# Proto-Pi-B.net
KiCad netlist of a schematic drawn in EAGLE
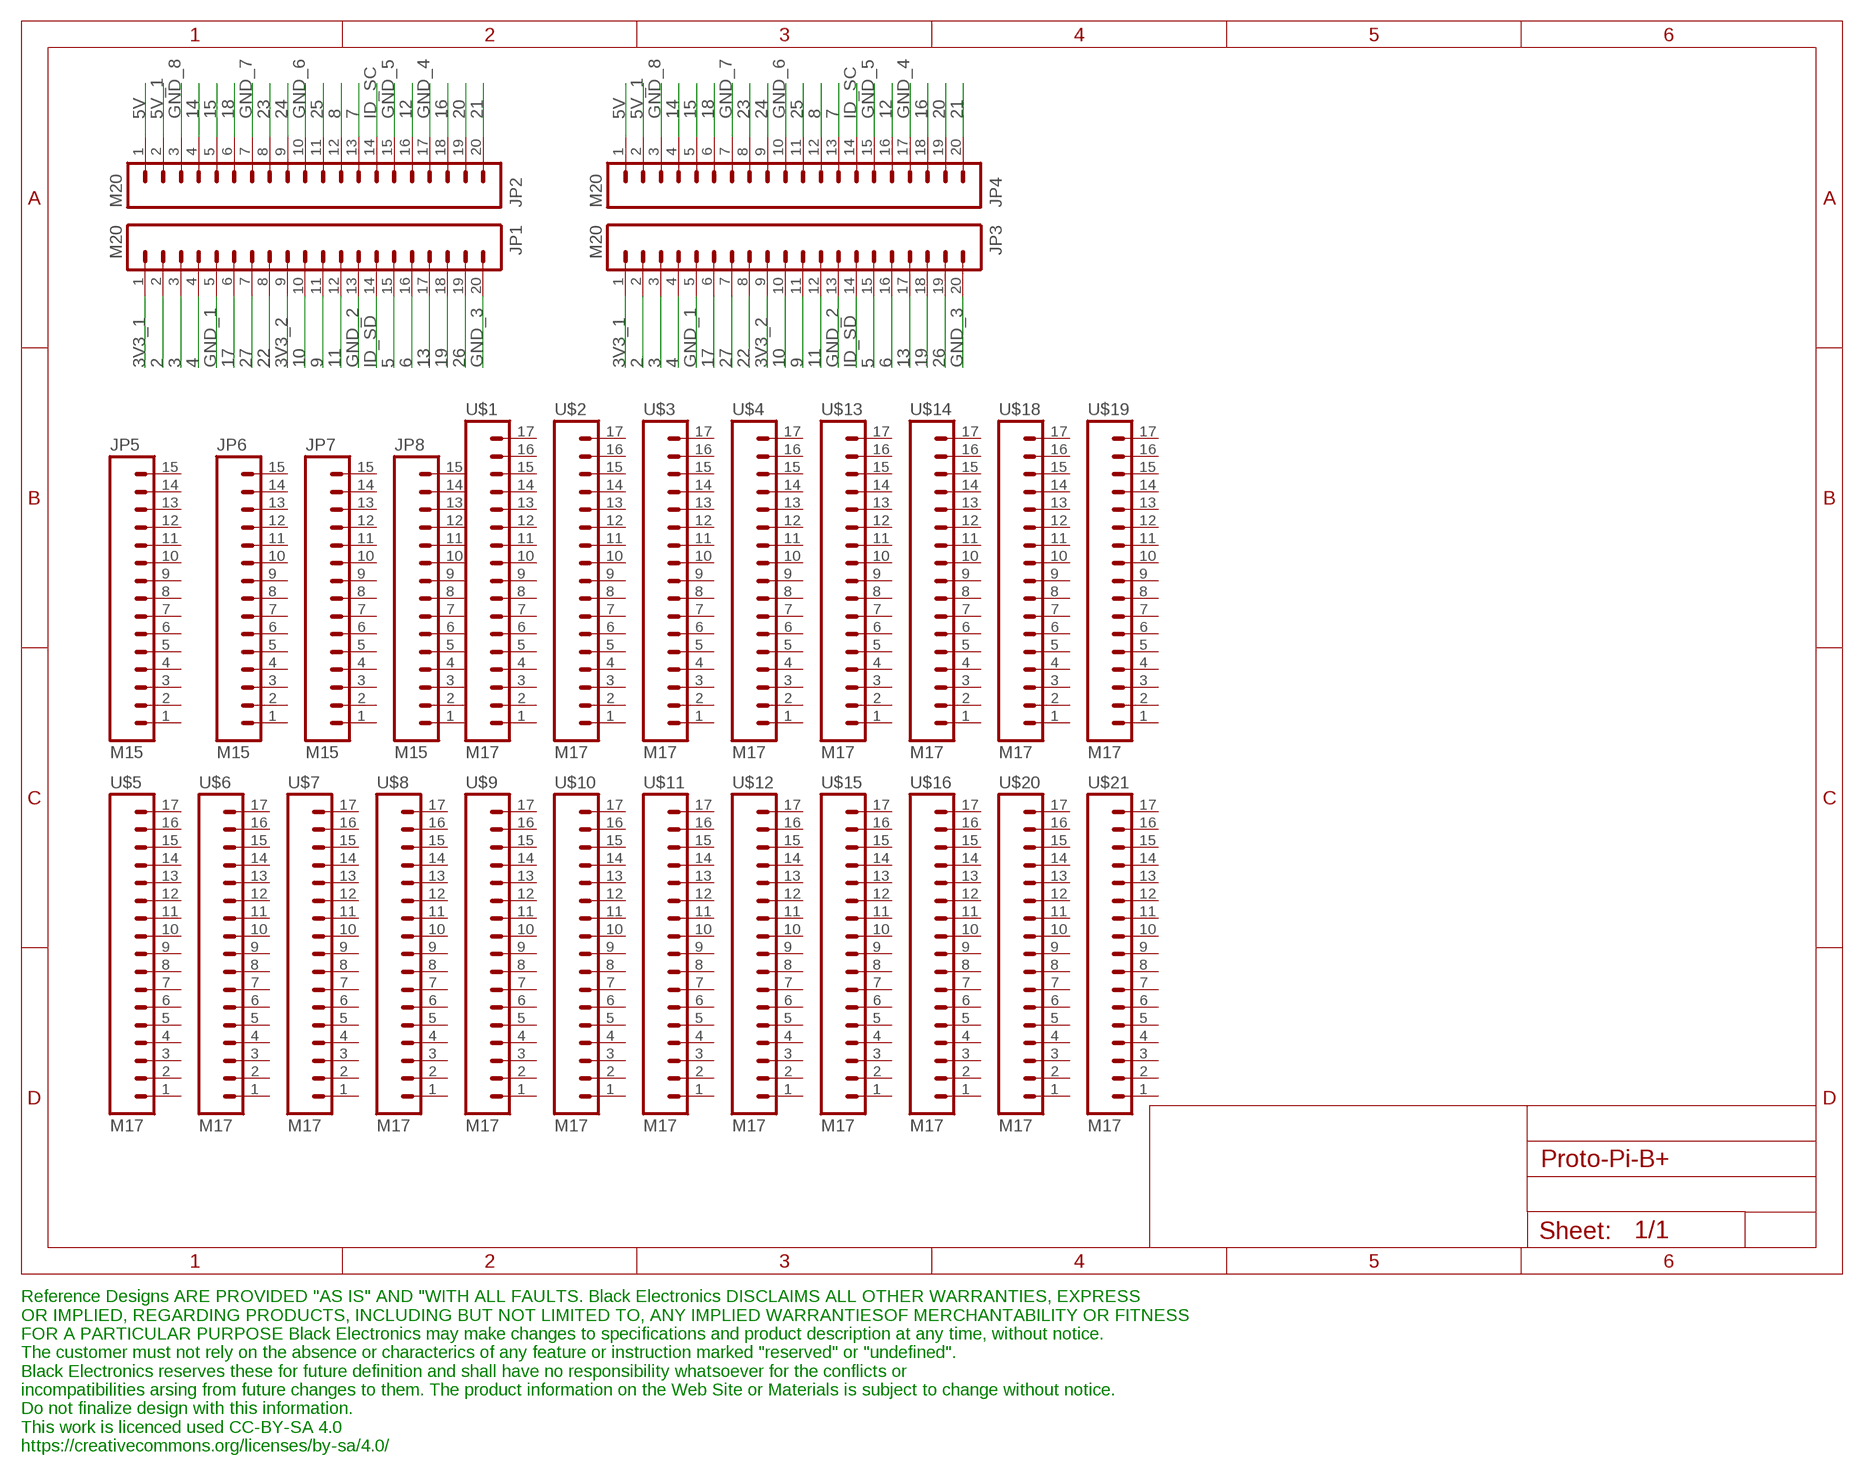
[diagram p0: schematic, sheet 1]

(export (version "E")
  (design (tool "Eeschema 10.0.6"))
  (components
    (comp (ref "JP1")
      (value "M20")
      (footprint "eagle-import:1X20")
      (libsource (lib "eagle-import") (part "M20"))
    )
    (comp (ref "JP2")
      (value "M20")
      (footprint "eagle-import:1X20")
      (libsource (lib "eagle-import") (part "M20"))
    )
    (comp (ref "JP3")
      (value "M20")
      (footprint "eagle-import:1X20")
      (libsource (lib "eagle-import") (part "M20"))
    )
    (comp (ref "JP4")
      (value "M20")
      (footprint "eagle-import:1X20")
      (libsource (lib "eagle-import") (part "M20"))
    )
    (comp (ref "JP5")
      (value "M15")
      (footprint "eagle-import:1X15")
      (libsource (lib "eagle-import") (part "M15"))
    )
    (comp (ref "JP6")
      (value "M15")
      (footprint "eagle-import:1X15")
      (libsource (lib "eagle-import") (part "M15"))
    )
    (comp (ref "JP7")
      (value "M15")
      (footprint "eagle-import:1X15")
      (libsource (lib "eagle-import") (part "M15"))
    )
    (comp (ref "JP8")
      (value "M15")
      (footprint "eagle-import:1X15")
      (libsource (lib "eagle-import") (part "M15"))
    )
    (comp (ref "U$1")
      (value "M17")
      (footprint "eagle-import:1X17")
      (libsource (lib "eagle-import") (part "M17"))
    )
    (comp (ref "U$2")
      (value "M17")
      (footprint "eagle-import:1X17")
      (libsource (lib "eagle-import") (part "M17"))
    )
    (comp (ref "U$3")
      (value "M17")
      (footprint "eagle-import:1X17")
      (libsource (lib "eagle-import") (part "M17"))
    )
    (comp (ref "U$4")
      (value "M17")
      (footprint "eagle-import:1X17")
      (libsource (lib "eagle-import") (part "M17"))
    )
    (comp (ref "U$5")
      (value "M17")
      (footprint "eagle-import:1X17")
      (libsource (lib "eagle-import") (part "M17"))
    )
    (comp (ref "U$6")
      (value "M17")
      (footprint "eagle-import:1X17")
      (libsource (lib "eagle-import") (part "M17"))
    )
    (comp (ref "U$7")
      (value "M17")
      (footprint "eagle-import:1X17")
      (libsource (lib "eagle-import") (part "M17"))
    )
    (comp (ref "U$8")
      (value "M17")
      (footprint "eagle-import:1X17")
      (libsource (lib "eagle-import") (part "M17"))
    )
    (comp (ref "U$9")
      (value "M17")
      (footprint "eagle-import:1X17")
      (libsource (lib "eagle-import") (part "M17"))
    )
    (comp (ref "U$10")
      (value "M17")
      (footprint "eagle-import:1X17")
      (libsource (lib "eagle-import") (part "M17"))
    )
    (comp (ref "U$11")
      (value "M17")
      (footprint "eagle-import:1X17")
      (libsource (lib "eagle-import") (part "M17"))
    )
    (comp (ref "U$12")
      (value "M17")
      (footprint "eagle-import:1X17")
      (libsource (lib "eagle-import") (part "M17"))
    )
    (comp (ref "U$13")
      (value "M17")
      (footprint "eagle-import:1X17")
      (libsource (lib "eagle-import") (part "M17"))
    )
    (comp (ref "U$14")
      (value "M17")
      (footprint "eagle-import:1X17")
      (libsource (lib "eagle-import") (part "M17"))
    )
    (comp (ref "U$15")
      (value "M17")
      (footprint "eagle-import:1X17")
      (libsource (lib "eagle-import") (part "M17"))
    )
    (comp (ref "U$16")
      (value "M17")
      (footprint "eagle-import:1X17")
      (libsource (lib "eagle-import") (part "M17"))
    )
    (comp (ref "U$18")
      (value "M17")
      (footprint "eagle-import:1X17")
      (libsource (lib "eagle-import") (part "M17"))
    )
    (comp (ref "U$19")
      (value "M17")
      (footprint "eagle-import:1X17")
      (libsource (lib "eagle-import") (part "M17"))
    )
    (comp (ref "U$20")
      (value "M17")
      (footprint "eagle-import:1X17")
      (libsource (lib "eagle-import") (part "M17"))
    )
    (comp (ref "U$21")
      (value "M17")
      (footprint "eagle-import:1X17")
      (libsource (lib "eagle-import") (part "M17"))
    )
  )
  (nets
    (net (code "1") (name "/2") (class "Default")
      (node (ref "JP1") (pin "2") (pinfunction "2_2") (pintype "passive"))
      (node (ref "JP3") (pin "2") (pinfunction "2_2") (pintype "passive"))
    )
    (net (code "2") (name "/3") (class "Default")
      (node (ref "JP1") (pin "3") (pinfunction "3_3") (pintype "passive"))
      (node (ref "JP3") (pin "3") (pinfunction "3_3") (pintype "passive"))
    )
    (net (code "3") (name "/3V3_1") (class "Default")
      (node (ref "JP1") (pin "1") (pinfunction "1_1") (pintype "passive"))
      (node (ref "JP3") (pin "1") (pinfunction "1_1") (pintype "passive"))
    )
    (net (code "4") (name "/3V3_2") (class "Default")
      (node (ref "JP1") (pin "9") (pinfunction "9_9") (pintype "passive"))
      (node (ref "JP3") (pin "9") (pinfunction "9_9") (pintype "passive"))
    )
    (net (code "5") (name "/4") (class "Default")
      (node (ref "JP1") (pin "4") (pinfunction "4_4") (pintype "passive"))
      (node (ref "JP3") (pin "4") (pinfunction "4_4") (pintype "passive"))
    )
    (net (code "6") (name "/5") (class "Default")
      (node (ref "JP1") (pin "15") (pinfunction "15_15") (pintype "passive"))
      (node (ref "JP3") (pin "15") (pinfunction "15_15") (pintype "passive"))
    )
    (net (code "7") (name "/5V") (class "Default")
      (node (ref "JP2") (pin "1") (pinfunction "1_1") (pintype "passive"))
      (node (ref "JP4") (pin "1") (pinfunction "1_1") (pintype "passive"))
    )
    (net (code "8") (name "/5V_1") (class "Default")
      (node (ref "JP2") (pin "2") (pinfunction "2_2") (pintype "passive"))
      (node (ref "JP4") (pin "2") (pinfunction "2_2") (pintype "passive"))
    )
    (net (code "9") (name "/6") (class "Default")
      (node (ref "JP1") (pin "16") (pinfunction "16_16") (pintype "passive"))
      (node (ref "JP3") (pin "16") (pinfunction "16_16") (pintype "passive"))
    )
    (net (code "10") (name "/7") (class "Default")
      (node (ref "JP2") (pin "13") (pinfunction "13_13") (pintype "passive"))
      (node (ref "JP4") (pin "13") (pinfunction "13_13") (pintype "passive"))
    )
    (net (code "11") (name "/8") (class "Default")
      (node (ref "JP2") (pin "12") (pinfunction "12_12") (pintype "passive"))
      (node (ref "JP4") (pin "12") (pinfunction "12_12") (pintype "passive"))
    )
    (net (code "12") (name "/9") (class "Default")
      (node (ref "JP1") (pin "11") (pinfunction "11_11") (pintype "passive"))
      (node (ref "JP3") (pin "11") (pinfunction "11_11") (pintype "passive"))
    )
    (net (code "13") (name "/10") (class "Default")
      (node (ref "JP1") (pin "10") (pinfunction "10_10") (pintype "passive"))
      (node (ref "JP3") (pin "10") (pinfunction "10_10") (pintype "passive"))
    )
    (net (code "14") (name "/11") (class "Default")
      (node (ref "JP1") (pin "12") (pinfunction "12_12") (pintype "passive"))
      (node (ref "JP3") (pin "12") (pinfunction "12_12") (pintype "passive"))
    )
    (net (code "15") (name "/12") (class "Default")
      (node (ref "JP2") (pin "16") (pinfunction "16_16") (pintype "passive"))
      (node (ref "JP4") (pin "16") (pinfunction "16_16") (pintype "passive"))
    )
    (net (code "16") (name "/13") (class "Default")
      (node (ref "JP1") (pin "17") (pinfunction "17_17") (pintype "passive"))
      (node (ref "JP3") (pin "17") (pinfunction "17_17") (pintype "passive"))
    )
    (net (code "17") (name "/14") (class "Default")
      (node (ref "JP2") (pin "4") (pinfunction "4_4") (pintype "passive"))
      (node (ref "JP4") (pin "4") (pinfunction "4_4") (pintype "passive"))
    )
    (net (code "18") (name "/15") (class "Default")
      (node (ref "JP2") (pin "5") (pinfunction "5_5") (pintype "passive"))
      (node (ref "JP4") (pin "5") (pinfunction "5_5") (pintype "passive"))
    )
    (net (code "19") (name "/16") (class "Default")
      (node (ref "JP2") (pin "18") (pinfunction "18_18") (pintype "passive"))
      (node (ref "JP4") (pin "18") (pinfunction "18_18") (pintype "passive"))
    )
    (net (code "20") (name "/17") (class "Default")
      (node (ref "JP1") (pin "6") (pinfunction "6_6") (pintype "passive"))
      (node (ref "JP3") (pin "6") (pinfunction "6_6") (pintype "passive"))
    )
    (net (code "21") (name "/18") (class "Default")
      (node (ref "JP2") (pin "6") (pinfunction "6_6") (pintype "passive"))
      (node (ref "JP4") (pin "6") (pinfunction "6_6") (pintype "passive"))
    )
    (net (code "22") (name "/19") (class "Default")
      (node (ref "JP1") (pin "18") (pinfunction "18_18") (pintype "passive"))
      (node (ref "JP3") (pin "18") (pinfunction "18_18") (pintype "passive"))
    )
    (net (code "23") (name "/20") (class "Default")
      (node (ref "JP2") (pin "19") (pinfunction "19_19") (pintype "passive"))
      (node (ref "JP4") (pin "19") (pinfunction "19_19") (pintype "passive"))
    )
    (net (code "24") (name "/21") (class "Default")
      (node (ref "JP2") (pin "20") (pinfunction "20_20") (pintype "passive"))
      (node (ref "JP4") (pin "20") (pinfunction "20_20") (pintype "passive"))
    )
    (net (code "25") (name "/22") (class "Default")
      (node (ref "JP1") (pin "8") (pinfunction "8_8") (pintype "passive"))
      (node (ref "JP3") (pin "8") (pinfunction "8_8") (pintype "passive"))
    )
    (net (code "26") (name "/23") (class "Default")
      (node (ref "JP2") (pin "8") (pinfunction "8_8") (pintype "passive"))
      (node (ref "JP4") (pin "8") (pinfunction "8_8") (pintype "passive"))
    )
    (net (code "27") (name "/24") (class "Default")
      (node (ref "JP2") (pin "9") (pinfunction "9_9") (pintype "passive"))
      (node (ref "JP4") (pin "9") (pinfunction "9_9") (pintype "passive"))
    )
    (net (code "28") (name "/25") (class "Default")
      (node (ref "JP2") (pin "11") (pinfunction "11_11") (pintype "passive"))
      (node (ref "JP4") (pin "11") (pinfunction "11_11") (pintype "passive"))
    )
    (net (code "29") (name "/26") (class "Default")
      (node (ref "JP1") (pin "19") (pinfunction "19_19") (pintype "passive"))
      (node (ref "JP3") (pin "19") (pinfunction "19_19") (pintype "passive"))
    )
    (net (code "30") (name "/27") (class "Default")
      (node (ref "JP1") (pin "7") (pinfunction "7_7") (pintype "passive"))
      (node (ref "JP3") (pin "7") (pinfunction "7_7") (pintype "passive"))
    )
    (net (code "31") (name "/GND_1") (class "Default")
      (node (ref "JP1") (pin "5") (pinfunction "5_5") (pintype "passive"))
      (node (ref "JP3") (pin "5") (pinfunction "5_5") (pintype "passive"))
    )
    (net (code "32") (name "/GND_2") (class "Default")
      (node (ref "JP1") (pin "13") (pinfunction "13_13") (pintype "passive"))
      (node (ref "JP3") (pin "13") (pinfunction "13_13") (pintype "passive"))
    )
    (net (code "33") (name "/GND_3") (class "Default")
      (node (ref "JP1") (pin "20") (pinfunction "20_20") (pintype "passive"))
      (node (ref "JP3") (pin "20") (pinfunction "20_20") (pintype "passive"))
    )
    (net (code "34") (name "/GND_4") (class "Default")
      (node (ref "JP2") (pin "17") (pinfunction "17_17") (pintype "passive"))
      (node (ref "JP4") (pin "17") (pinfunction "17_17") (pintype "passive"))
    )
    (net (code "35") (name "/GND_5") (class "Default")
      (node (ref "JP2") (pin "15") (pinfunction "15_15") (pintype "passive"))
      (node (ref "JP4") (pin "15") (pinfunction "15_15") (pintype "passive"))
    )
    (net (code "36") (name "/GND_6") (class "Default")
      (node (ref "JP2") (pin "10") (pinfunction "10_10") (pintype "passive"))
      (node (ref "JP4") (pin "10") (pinfunction "10_10") (pintype "passive"))
    )
    (net (code "37") (name "/GND_7") (class "Default")
      (node (ref "JP2") (pin "7") (pinfunction "7_7") (pintype "passive"))
      (node (ref "JP4") (pin "7") (pinfunction "7_7") (pintype "passive"))
    )
    (net (code "38") (name "/GND_8") (class "Default")
      (node (ref "JP2") (pin "3") (pinfunction "3_3") (pintype "passive"))
      (node (ref "JP4") (pin "3") (pinfunction "3_3") (pintype "passive"))
    )
    (net (code "39") (name "/ID_SC") (class "Default")
      (node (ref "JP2") (pin "14") (pinfunction "14_14") (pintype "passive"))
      (node (ref "JP4") (pin "14") (pinfunction "14_14") (pintype "passive"))
    )
    (net (code "40") (name "/ID_SD") (class "Default")
      (node (ref "JP1") (pin "14") (pinfunction "14_14") (pintype "passive"))
      (node (ref "JP3") (pin "14") (pinfunction "14_14") (pintype "passive"))
    )
    (net (code "41") (name "unconnected-(JP5-Pad1)") (class "Default")
      (node (ref "JP5") (pin "1") (pinfunction "1_1") (pintype "passive"))
    )
    (net (code "42") (name "unconnected-(JP5-Pad2)") (class "Default")
      (node (ref "JP5") (pin "2") (pinfunction "2_2") (pintype "passive"))
    )
    (net (code "43") (name "unconnected-(JP5-Pad3)") (class "Default")
      (node (ref "JP5") (pin "3") (pinfunction "3_3") (pintype "passive"))
    )
    (net (code "44") (name "unconnected-(JP5-Pad4)") (class "Default")
      (node (ref "JP5") (pin "4") (pinfunction "4_4") (pintype "passive"))
    )
    (net (code "45") (name "unconnected-(JP5-Pad5)") (class "Default")
      (node (ref "JP5") (pin "5") (pinfunction "5_5") (pintype "passive"))
    )
    (net (code "46") (name "unconnected-(JP5-Pad6)") (class "Default")
      (node (ref "JP5") (pin "6") (pinfunction "6_6") (pintype "passive"))
    )
    (net (code "47") (name "unconnected-(JP5-Pad7)") (class "Default")
      (node (ref "JP5") (pin "7") (pinfunction "7_7") (pintype "passive"))
    )
    (net (code "48") (name "unconnected-(JP5-Pad8)") (class "Default")
      (node (ref "JP5") (pin "8") (pinfunction "8_8") (pintype "passive"))
    )
    (net (code "49") (name "unconnected-(JP5-Pad9)") (class "Default")
      (node (ref "JP5") (pin "9") (pinfunction "9_9") (pintype "passive"))
    )
    (net (code "50") (name "unconnected-(JP5-Pad10)") (class "Default")
      (node (ref "JP5") (pin "10") (pinfunction "10_10") (pintype "passive"))
    )
    (net (code "51") (name "unconnected-(JP5-Pad11)") (class "Default")
      (node (ref "JP5") (pin "11") (pinfunction "11_11") (pintype "passive"))
    )
    (net (code "52") (name "unconnected-(JP5-Pad12)") (class "Default")
      (node (ref "JP5") (pin "12") (pinfunction "12_12") (pintype "passive"))
    )
    (net (code "53") (name "unconnected-(JP5-Pad13)") (class "Default")
      (node (ref "JP5") (pin "13") (pinfunction "13_13") (pintype "passive"))
    )
    (net (code "54") (name "unconnected-(JP5-Pad14)") (class "Default")
      (node (ref "JP5") (pin "14") (pinfunction "14_14") (pintype "passive"))
    )
    (net (code "55") (name "unconnected-(JP5-Pad15)") (class "Default")
      (node (ref "JP5") (pin "15") (pinfunction "15_15") (pintype "passive"))
    )
    (net (code "56") (name "unconnected-(JP6-Pad1)") (class "Default")
      (node (ref "JP6") (pin "1") (pinfunction "1_1") (pintype "passive"))
    )
    (net (code "57") (name "unconnected-(JP6-Pad2)") (class "Default")
      (node (ref "JP6") (pin "2") (pinfunction "2_2") (pintype "passive"))
    )
    (net (code "58") (name "unconnected-(JP6-Pad3)") (class "Default")
      (node (ref "JP6") (pin "3") (pinfunction "3_3") (pintype "passive"))
    )
    (net (code "59") (name "unconnected-(JP6-Pad4)") (class "Default")
      (node (ref "JP6") (pin "4") (pinfunction "4_4") (pintype "passive"))
    )
    (net (code "60") (name "unconnected-(JP6-Pad5)") (class "Default")
      (node (ref "JP6") (pin "5") (pinfunction "5_5") (pintype "passive"))
    )
    (net (code "61") (name "unconnected-(JP6-Pad6)") (class "Default")
      (node (ref "JP6") (pin "6") (pinfunction "6_6") (pintype "passive"))
    )
    (net (code "62") (name "unconnected-(JP6-Pad7)") (class "Default")
      (node (ref "JP6") (pin "7") (pinfunction "7_7") (pintype "passive"))
    )
    (net (code "63") (name "unconnected-(JP6-Pad8)") (class "Default")
      (node (ref "JP6") (pin "8") (pinfunction "8_8") (pintype "passive"))
    )
    (net (code "64") (name "unconnected-(JP6-Pad9)") (class "Default")
      (node (ref "JP6") (pin "9") (pinfunction "9_9") (pintype "passive"))
    )
    (net (code "65") (name "unconnected-(JP6-Pad10)") (class "Default")
      (node (ref "JP6") (pin "10") (pinfunction "10_10") (pintype "passive"))
    )
    (net (code "66") (name "unconnected-(JP6-Pad11)") (class "Default")
      (node (ref "JP6") (pin "11") (pinfunction "11_11") (pintype "passive"))
    )
    (net (code "67") (name "unconnected-(JP6-Pad12)") (class "Default")
      (node (ref "JP6") (pin "12") (pinfunction "12_12") (pintype "passive"))
    )
    (net (code "68") (name "unconnected-(JP6-Pad13)") (class "Default")
      (node (ref "JP6") (pin "13") (pinfunction "13_13") (pintype "passive"))
    )
    (net (code "69") (name "unconnected-(JP6-Pad14)") (class "Default")
      (node (ref "JP6") (pin "14") (pinfunction "14_14") (pintype "passive"))
    )
    (net (code "70") (name "unconnected-(JP6-Pad15)") (class "Default")
      (node (ref "JP6") (pin "15") (pinfunction "15_15") (pintype "passive"))
    )
    (net (code "71") (name "unconnected-(JP7-Pad1)") (class "Default")
      (node (ref "JP7") (pin "1") (pinfunction "1_1") (pintype "passive"))
    )
    (net (code "72") (name "unconnected-(JP7-Pad2)") (class "Default")
      (node (ref "JP7") (pin "2") (pinfunction "2_2") (pintype "passive"))
    )
    (net (code "73") (name "unconnected-(JP7-Pad3)") (class "Default")
      (node (ref "JP7") (pin "3") (pinfunction "3_3") (pintype "passive"))
    )
    (net (code "74") (name "unconnected-(JP7-Pad4)") (class "Default")
      (node (ref "JP7") (pin "4") (pinfunction "4_4") (pintype "passive"))
    )
    (net (code "75") (name "unconnected-(JP7-Pad5)") (class "Default")
      (node (ref "JP7") (pin "5") (pinfunction "5_5") (pintype "passive"))
    )
    (net (code "76") (name "unconnected-(JP7-Pad6)") (class "Default")
      (node (ref "JP7") (pin "6") (pinfunction "6_6") (pintype "passive"))
    )
    (net (code "77") (name "unconnected-(JP7-Pad7)") (class "Default")
      (node (ref "JP7") (pin "7") (pinfunction "7_7") (pintype "passive"))
    )
    (net (code "78") (name "unconnected-(JP7-Pad8)") (class "Default")
      (node (ref "JP7") (pin "8") (pinfunction "8_8") (pintype "passive"))
    )
    (net (code "79") (name "unconnected-(JP7-Pad9)") (class "Default")
      (node (ref "JP7") (pin "9") (pinfunction "9_9") (pintype "passive"))
    )
    (net (code "80") (name "unconnected-(JP7-Pad10)") (class "Default")
      (node (ref "JP7") (pin "10") (pinfunction "10_10") (pintype "passive"))
    )
    (net (code "81") (name "unconnected-(JP7-Pad11)") (class "Default")
      (node (ref "JP7") (pin "11") (pinfunction "11_11") (pintype "passive"))
    )
    (net (code "82") (name "unconnected-(JP7-Pad12)") (class "Default")
      (node (ref "JP7") (pin "12") (pinfunction "12_12") (pintype "passive"))
    )
    (net (code "83") (name "unconnected-(JP7-Pad13)") (class "Default")
      (node (ref "JP7") (pin "13") (pinfunction "13_13") (pintype "passive"))
    )
    (net (code "84") (name "unconnected-(JP7-Pad14)") (class "Default")
      (node (ref "JP7") (pin "14") (pinfunction "14_14") (pintype "passive"))
    )
    (net (code "85") (name "unconnected-(JP7-Pad15)") (class "Default")
      (node (ref "JP7") (pin "15") (pinfunction "15_15") (pintype "passive"))
    )
    (net (code "86") (name "unconnected-(JP8-Pad1)") (class "Default")
      (node (ref "JP8") (pin "1") (pinfunction "1_1") (pintype "passive"))
    )
    (net (code "87") (name "unconnected-(JP8-Pad2)") (class "Default")
      (node (ref "JP8") (pin "2") (pinfunction "2_2") (pintype "passive"))
    )
    (net (code "88") (name "unconnected-(JP8-Pad3)") (class "Default")
      (node (ref "JP8") (pin "3") (pinfunction "3_3") (pintype "passive"))
    )
    (net (code "89") (name "unconnected-(JP8-Pad4)") (class "Default")
      (node (ref "JP8") (pin "4") (pinfunction "4_4") (pintype "passive"))
    )
    (net (code "90") (name "unconnected-(JP8-Pad5)") (class "Default")
      (node (ref "JP8") (pin "5") (pinfunction "5_5") (pintype "passive"))
    )
    (net (code "91") (name "unconnected-(JP8-Pad6)") (class "Default")
      (node (ref "JP8") (pin "6") (pinfunction "6_6") (pintype "passive"))
    )
    (net (code "92") (name "unconnected-(JP8-Pad7)") (class "Default")
      (node (ref "JP8") (pin "7") (pinfunction "7_7") (pintype "passive"))
    )
    (net (code "93") (name "unconnected-(JP8-Pad8)") (class "Default")
      (node (ref "JP8") (pin "8") (pinfunction "8_8") (pintype "passive"))
    )
    (net (code "94") (name "unconnected-(JP8-Pad9)") (class "Default")
      (node (ref "JP8") (pin "9") (pinfunction "9_9") (pintype "passive"))
    )
    (net (code "95") (name "unconnected-(JP8-Pad10)") (class "Default")
      (node (ref "JP8") (pin "10") (pinfunction "10_10") (pintype "passive"))
    )
    (net (code "96") (name "unconnected-(JP8-Pad11)") (class "Default")
      (node (ref "JP8") (pin "11") (pinfunction "11_11") (pintype "passive"))
    )
    (net (code "97") (name "unconnected-(JP8-Pad12)") (class "Default")
      (node (ref "JP8") (pin "12") (pinfunction "12_12") (pintype "passive"))
    )
    (net (code "98") (name "unconnected-(JP8-Pad13)") (class "Default")
      (node (ref "JP8") (pin "13") (pinfunction "13_13") (pintype "passive"))
    )
    (net (code "99") (name "unconnected-(JP8-Pad14)") (class "Default")
      (node (ref "JP8") (pin "14") (pinfunction "14_14") (pintype "passive"))
    )
    (net (code "100") (name "unconnected-(JP8-Pad15)") (class "Default")
      (node (ref "JP8") (pin "15") (pinfunction "15_15") (pintype "passive"))
    )
    (net (code "101") (name "unconnected-(U$1-Pad1)") (class "Default")
      (node (ref "U$1") (pin "1") (pinfunction "1_1") (pintype "passive"))
    )
    (net (code "102") (name "unconnected-(U$1-Pad2)") (class "Default")
      (node (ref "U$1") (pin "2") (pinfunction "2_2") (pintype "passive"))
    )
    (net (code "103") (name "unconnected-(U$1-Pad3)") (class "Default")
      (node (ref "U$1") (pin "3") (pinfunction "3_3") (pintype "passive"))
    )
    (net (code "104") (name "unconnected-(U$1-Pad4)") (class "Default")
      (node (ref "U$1") (pin "4") (pinfunction "4_4") (pintype "passive"))
    )
    (net (code "105") (name "unconnected-(U$1-Pad5)") (class "Default")
      (node (ref "U$1") (pin "5") (pinfunction "5_5") (pintype "passive"))
    )
    (net (code "106") (name "unconnected-(U$1-Pad6)") (class "Default")
      (node (ref "U$1") (pin "6") (pinfunction "6_6") (pintype "passive"))
    )
    (net (code "107") (name "unconnected-(U$1-Pad7)") (class "Default")
      (node (ref "U$1") (pin "7") (pinfunction "7_7") (pintype "passive"))
    )
    (net (code "108") (name "unconnected-(U$1-Pad8)") (class "Default")
      (node (ref "U$1") (pin "8") (pinfunction "8_8") (pintype "passive"))
    )
    (net (code "109") (name "unconnected-(U$1-Pad9)") (class "Default")
      (node (ref "U$1") (pin "9") (pinfunction "9_9") (pintype "passive"))
    )
    (net (code "110") (name "unconnected-(U$1-Pad10)") (class "Default")
      (node (ref "U$1") (pin "10") (pinfunction "10_10") (pintype "passive"))
    )
    (net (code "111") (name "unconnected-(U$1-Pad11)") (class "Default")
      (node (ref "U$1") (pin "11") (pinfunction "11_11") (pintype "passive"))
    )
    (net (code "112") (name "unconnected-(U$1-Pad12)") (class "Default")
      (node (ref "U$1") (pin "12") (pinfunction "12_12") (pintype "passive"))
    )
    (net (code "113") (name "unconnected-(U$1-Pad13)") (class "Default")
      (node (ref "U$1") (pin "13") (pinfunction "13_13") (pintype "passive"))
    )
    (net (code "114") (name "unconnected-(U$1-Pad14)") (class "Default")
      (node (ref "U$1") (pin "14") (pinfunction "14_14") (pintype "passive"))
    )
    (net (code "115") (name "unconnected-(U$1-Pad15)") (class "Default")
      (node (ref "U$1") (pin "15") (pinfunction "15_15") (pintype "passive"))
    )
    (net (code "116") (name "unconnected-(U$1-Pad16)") (class "Default")
      (node (ref "U$1") (pin "16") (pinfunction "16_16") (pintype "passive"))
    )
    (net (code "117") (name "unconnected-(U$1-Pad17)") (class "Default")
      (node (ref "U$1") (pin "17") (pinfunction "17_17") (pintype "passive"))
    )
    (net (code "118") (name "unconnected-(U$2-Pad1)") (class "Default")
      (node (ref "U$2") (pin "1") (pinfunction "1_1") (pintype "passive"))
    )
    (net (code "119") (name "unconnected-(U$2-Pad2)") (class "Default")
      (node (ref "U$2") (pin "2") (pinfunction "2_2") (pintype "passive"))
    )
    (net (code "120") (name "unconnected-(U$2-Pad3)") (class "Default")
      (node (ref "U$2") (pin "3") (pinfunction "3_3") (pintype "passive"))
    )
    (net (code "121") (name "unconnected-(U$2-Pad4)") (class "Default")
      (node (ref "U$2") (pin "4") (pinfunction "4_4") (pintype "passive"))
    )
    (net (code "122") (name "unconnected-(U$2-Pad5)") (class "Default")
      (node (ref "U$2") (pin "5") (pinfunction "5_5") (pintype "passive"))
    )
    (net (code "123") (name "unconnected-(U$2-Pad6)") (class "Default")
      (node (ref "U$2") (pin "6") (pinfunction "6_6") (pintype "passive"))
    )
    (net (code "124") (name "unconnected-(U$2-Pad7)") (class "Default")
      (node (ref "U$2") (pin "7") (pinfunction "7_7") (pintype "passive"))
    )
    (net (code "125") (name "unconnected-(U$2-Pad8)") (class "Default")
      (node (ref "U$2") (pin "8") (pinfunction "8_8") (pintype "passive"))
    )
    (net (code "126") (name "unconnected-(U$2-Pad9)") (class "Default")
      (node (ref "U$2") (pin "9") (pinfunction "9_9") (pintype "passive"))
    )
    (net (code "127") (name "unconnected-(U$2-Pad10)") (class "Default")
      (node (ref "U$2") (pin "10") (pinfunction "10_10") (pintype "passive"))
    )
    (net (code "128") (name "unconnected-(U$2-Pad11)") (class "Default")
      (node (ref "U$2") (pin "11") (pinfunction "11_11") (pintype "passive"))
    )
    (net (code "129") (name "unconnected-(U$2-Pad12)") (class "Default")
      (node (ref "U$2") (pin "12") (pinfunction "12_12") (pintype "passive"))
    )
    (net (code "130") (name "unconnected-(U$2-Pad13)") (class "Default")
      (node (ref "U$2") (pin "13") (pinfunction "13_13") (pintype "passive"))
    )
    (net (code "131") (name "unconnected-(U$2-Pad14)") (class "Default")
      (node (ref "U$2") (pin "14") (pinfunction "14_14") (pintype "passive"))
    )
    (net (code "132") (name "unconnected-(U$2-Pad15)") (class "Default")
      (node (ref "U$2") (pin "15") (pinfunction "15_15") (pintype "passive"))
    )
    (net (code "133") (name "unconnected-(U$2-Pad16)") (class "Default")
      (node (ref "U$2") (pin "16") (pinfunction "16_16") (pintype "passive"))
    )
    (net (code "134") (name "unconnected-(U$2-Pad17)") (class "Default")
      (node (ref "U$2") (pin "17") (pinfunction "17_17") (pintype "passive"))
    )
    (net (code "135") (name "unconnected-(U$3-Pad1)") (class "Default")
      (node (ref "U$3") (pin "1") (pinfunction "1_1") (pintype "passive"))
    )
    (net (code "136") (name "unconnected-(U$3-Pad2)") (class "Default")
      (node (ref "U$3") (pin "2") (pinfunction "2_2") (pintype "passive"))
    )
    (net (code "137") (name "unconnected-(U$3-Pad3)") (class "Default")
      (node (ref "U$3") (pin "3") (pinfunction "3_3") (pintype "passive"))
    )
    (net (code "138") (name "unconnected-(U$3-Pad4)") (class "Default")
      (node (ref "U$3") (pin "4") (pinfunction "4_4") (pintype "passive"))
    )
    (net (code "139") (name "unconnected-(U$3-Pad5)") (class "Default")
      (node (ref "U$3") (pin "5") (pinfunction "5_5") (pintype "passive"))
    )
    (net (code "140") (name "unconnected-(U$3-Pad6)") (class "Default")
      (node (ref "U$3") (pin "6") (pinfunction "6_6") (pintype "passive"))
    )
    (net (code "141") (name "unconnected-(U$3-Pad7)") (class "Default")
      (node (ref "U$3") (pin "7") (pinfunction "7_7") (pintype "passive"))
    )
    (net (code "142") (name "unconnected-(U$3-Pad8)") (class "Default")
      (node (ref "U$3") (pin "8") (pinfunction "8_8") (pintype "passive"))
    )
    (net (code "143") (name "unconnected-(U$3-Pad9)") (class "Default")
      (node (ref "U$3") (pin "9") (pinfunction "9_9") (pintype "passive"))
    )
    (net (code "144") (name "unconnected-(U$3-Pad10)") (class "Default")
      (node (ref "U$3") (pin "10") (pinfunction "10_10") (pintype "passive"))
    )
    (net (code "145") (name "unconnected-(U$3-Pad11)") (class "Default")
      (node (ref "U$3") (pin "11") (pinfunction "11_11") (pintype "passive"))
    )
    (net (code "146") (name "unconnected-(U$3-Pad12)") (class "Default")
      (node (ref "U$3") (pin "12") (pinfunction "12_12") (pintype "passive"))
    )
    (net (code "147") (name "unconnected-(U$3-Pad13)") (class "Default")
      (node (ref "U$3") (pin "13") (pinfunction "13_13") (pintype "passive"))
    )
    (net (code "148") (name "unconnected-(U$3-Pad14)") (class "Default")
      (node (ref "U$3") (pin "14") (pinfunction "14_14") (pintype "passive"))
    )
    (net (code "149") (name "unconnected-(U$3-Pad15)") (class "Default")
      (node (ref "U$3") (pin "15") (pinfunction "15_15") (pintype "passive"))
    )
    (net (code "150") (name "unconnected-(U$3-Pad16)") (class "Default")
      (node (ref "U$3") (pin "16") (pinfunction "16_16") (pintype "passive"))
    )
    (net (code "151") (name "unconnected-(U$3-Pad17)") (class "Default")
      (node (ref "U$3") (pin "17") (pinfunction "17_17") (pintype "passive"))
    )
    (net (code "152") (name "unconnected-(U$4-Pad1)") (class "Default")
      (node (ref "U$4") (pin "1") (pinfunction "1_1") (pintype "passive"))
    )
    (net (code "153") (name "unconnected-(U$4-Pad2)") (class "Default")
      (node (ref "U$4") (pin "2") (pinfunction "2_2") (pintype "passive"))
    )
    (net (code "154") (name "unconnected-(U$4-Pad3)") (class "Default")
      (node (ref "U$4") (pin "3") (pinfunction "3_3") (pintype "passive"))
    )
    (net (code "155") (name "unconnected-(U$4-Pad4)") (class "Default")
      (node (ref "U$4") (pin "4") (pinfunction "4_4") (pintype "passive"))
    )
    (net (code "156") (name "unconnected-(U$4-Pad5)") (class "Default")
      (node (ref "U$4") (pin "5") (pinfunction "5_5") (pintype "passive"))
    )
    (net (code "157") (name "unconnected-(U$4-Pad6)") (class "Default")
      (node (ref "U$4") (pin "6") (pinfunction "6_6") (pintype "passive"))
    )
    (net (code "158") (name "unconnected-(U$4-Pad7)") (class "Default")
      (node (ref "U$4") (pin "7") (pinfunction "7_7") (pintype "passive"))
    )
    (net (code "159") (name "unconnected-(U$4-Pad8)") (class "Default")
      (node (ref "U$4") (pin "8") (pinfunction "8_8") (pintype "passive"))
    )
    (net (code "160") (name "unconnected-(U$4-Pad9)") (class "Default")
      (node (ref "U$4") (pin "9") (pinfunction "9_9") (pintype "passive"))
    )
    (net (code "161") (name "unconnected-(U$4-Pad10)") (class "Default")
      (node (ref "U$4") (pin "10") (pinfunction "10_10") (pintype "passive"))
    )
    (net (code "162") (name "unconnected-(U$4-Pad11)") (class "Default")
      (node (ref "U$4") (pin "11") (pinfunction "11_11") (pintype "passive"))
    )
    (net (code "163") (name "unconnected-(U$4-Pad12)") (class "Default")
      (node (ref "U$4") (pin "12") (pinfunction "12_12") (pintype "passive"))
    )
    (net (code "164") (name "unconnected-(U$4-Pad13)") (class "Default")
      (node (ref "U$4") (pin "13") (pinfunction "13_13") (pintype "passive"))
    )
    (net (code "165") (name "unconnected-(U$4-Pad14)") (class "Default")
      (node (ref "U$4") (pin "14") (pinfunction "14_14") (pintype "passive"))
    )
    (net (code "166") (name "unconnected-(U$4-Pad15)") (class "Default")
      (node (ref "U$4") (pin "15") (pinfunction "15_15") (pintype "passive"))
    )
    (net (code "167") (name "unconnected-(U$4-Pad16)") (class "Default")
      (node (ref "U$4") (pin "16") (pinfunction "16_16") (pintype "passive"))
    )
    (net (code "168") (name "unconnected-(U$4-Pad17)") (class "Default")
      (node (ref "U$4") (pin "17") (pinfunction "17_17") (pintype "passive"))
    )
    (net (code "169") (name "unconnected-(U$5-Pad1)") (class "Default")
      (node (ref "U$5") (pin "1") (pinfunction "1_1") (pintype "passive"))
    )
    (net (code "170") (name "unconnected-(U$5-Pad2)") (class "Default")
      (node (ref "U$5") (pin "2") (pinfunction "2_2") (pintype "passive"))
    )
    (net (code "171") (name "unconnected-(U$5-Pad3)") (class "Default")
      (node (ref "U$5") (pin "3") (pinfunction "3_3") (pintype "passive"))
    )
    (net (code "172") (name "unconnected-(U$5-Pad4)") (class "Default")
      (node (ref "U$5") (pin "4") (pinfunction "4_4") (pintype "passive"))
    )
    (net (code "173") (name "unconnected-(U$5-Pad5)") (class "Default")
      (node (ref "U$5") (pin "5") (pinfunction "5_5") (pintype "passive"))
    )
    (net (code "174") (name "unconnected-(U$5-Pad6)") (class "Default")
      (node (ref "U$5") (pin "6") (pinfunction "6_6") (pintype "passive"))
    )
    (net (code "175") (name "unconnected-(U$5-Pad7)") (class "Default")
      (node (ref "U$5") (pin "7") (pinfunction "7_7") (pintype "passive"))
    )
    (net (code "176") (name "unconnected-(U$5-Pad8)") (class "Default")
      (node (ref "U$5") (pin "8") (pinfunction "8_8") (pintype "passive"))
    )
    (net (code "177") (name "unconnected-(U$5-Pad9)") (class "Default")
      (node (ref "U$5") (pin "9") (pinfunction "9_9") (pintype "passive"))
    )
    (net (code "178") (name "unconnected-(U$5-Pad10)") (class "Default")
      (node (ref "U$5") (pin "10") (pinfunction "10_10") (pintype "passive"))
    )
    (net (code "179") (name "unconnected-(U$5-Pad11)") (class "Default")
      (node (ref "U$5") (pin "11") (pinfunction "11_11") (pintype "passive"))
    )
    (net (code "180") (name "unconnected-(U$5-Pad12)") (class "Default")
      (node (ref "U$5") (pin "12") (pinfunction "12_12") (pintype "passive"))
    )
    (net (code "181") (name "unconnected-(U$5-Pad13)") (class "Default")
      (node (ref "U$5") (pin "13") (pinfunction "13_13") (pintype "passive"))
    )
    (net (code "182") (name "unconnected-(U$5-Pad14)") (class "Default")
      (node (ref "U$5") (pin "14") (pinfunction "14_14") (pintype "passive"))
    )
    (net (code "183") (name "unconnected-(U$5-Pad15)") (class "Default")
      (node (ref "U$5") (pin "15") (pinfunction "15_15") (pintype "passive"))
    )
    (net (code "184") (name "unconnected-(U$5-Pad16)") (class "Default")
      (node (ref "U$5") (pin "16") (pinfunction "16_16") (pintype "passive"))
    )
    (net (code "185") (name "unconnected-(U$5-Pad17)") (class "Default")
      (node (ref "U$5") (pin "17") (pinfunction "17_17") (pintype "passive"))
    )
    (net (code "186") (name "unconnected-(U$6-Pad1)") (class "Default")
      (node (ref "U$6") (pin "1") (pinfunction "1_1") (pintype "passive"))
    )
    (net (code "187") (name "unconnected-(U$6-Pad2)") (class "Default")
      (node (ref "U$6") (pin "2") (pinfunction "2_2") (pintype "passive"))
    )
    (net (code "188") (name "unconnected-(U$6-Pad3)") (class "Default")
      (node (ref "U$6") (pin "3") (pinfunction "3_3") (pintype "passive"))
    )
    (net (code "189") (name "unconnected-(U$6-Pad4)") (class "Default")
      (node (ref "U$6") (pin "4") (pinfunction "4_4") (pintype "passive"))
    )
    (net (code "190") (name "unconnected-(U$6-Pad5)") (class "Default")
      (node (ref "U$6") (pin "5") (pinfunction "5_5") (pintype "passive"))
    )
    (net (code "191") (name "unconnected-(U$6-Pad6)") (class "Default")
      (node (ref "U$6") (pin "6") (pinfunction "6_6") (pintype "passive"))
    )
    (net (code "192") (name "unconnected-(U$6-Pad7)") (class "Default")
      (node (ref "U$6") (pin "7") (pinfunction "7_7") (pintype "passive"))
    )
    (net (code "193") (name "unconnected-(U$6-Pad8)") (class "Default")
      (node (ref "U$6") (pin "8") (pinfunction "8_8") (pintype "passive"))
    )
    (net (code "194") (name "unconnected-(U$6-Pad9)") (class "Default")
      (node (ref "U$6") (pin "9") (pinfunction "9_9") (pintype "passive"))
    )
    (net (code "195") (name "unconnected-(U$6-Pad10)") (class "Default")
      (node (ref "U$6") (pin "10") (pinfunction "10_10") (pintype "passive"))
    )
    (net (code "196") (name "unconnected-(U$6-Pad11)") (class "Default")
      (node (ref "U$6") (pin "11") (pinfunction "11_11") (pintype "passive"))
    )
    (net (code "197") (name "unconnected-(U$6-Pad12)") (class "Default")
      (node (ref "U$6") (pin "12") (pinfunction "12_12") (pintype "passive"))
    )
    (net (code "198") (name "unconnected-(U$6-Pad13)") (class "Default")
      (node (ref "U$6") (pin "13") (pinfunction "13_13") (pintype "passive"))
    )
    (net (code "199") (name "unconnected-(U$6-Pad14)") (class "Default")
      (node (ref "U$6") (pin "14") (pinfunction "14_14") (pintype "passive"))
    )
    (net (code "200") (name "unconnected-(U$6-Pad15)") (class "Default")
      (node (ref "U$6") (pin "15") (pinfunction "15_15") (pintype "passive"))
    )
    (net (code "201") (name "unconnected-(U$6-Pad16)") (class "Default")
      (node (ref "U$6") (pin "16") (pinfunction "16_16") (pintype "passive"))
    )
    (net (code "202") (name "unconnected-(U$6-Pad17)") (class "Default")
      (node (ref "U$6") (pin "17") (pinfunction "17_17") (pintype "passive"))
    )
    (net (code "203") (name "unconnected-(U$7-Pad1)") (class "Default")
      (node (ref "U$7") (pin "1") (pinfunction "1_1") (pintype "passive"))
    )
    (net (code "204") (name "unconnected-(U$7-Pad2)") (class "Default")
      (node (ref "U$7") (pin "2") (pinfunction "2_2") (pintype "passive"))
    )
    (net (code "205") (name "unconnected-(U$7-Pad3)") (class "Default")
      (node (ref "U$7") (pin "3") (pinfunction "3_3") (pintype "passive"))
    )
    (net (code "206") (name "unconnected-(U$7-Pad4)") (class "Default")
      (node (ref "U$7") (pin "4") (pinfunction "4_4") (pintype "passive"))
    )
    (net (code "207") (name "unconnected-(U$7-Pad5)") (class "Default")
      (node (ref "U$7") (pin "5") (pinfunction "5_5") (pintype "passive"))
    )
    (net (code "208") (name "unconnected-(U$7-Pad6)") (class "Default")
      (node (ref "U$7") (pin "6") (pinfunction "6_6") (pintype "passive"))
    )
    (net (code "209") (name "unconnected-(U$7-Pad7)") (class "Default")
      (node (ref "U$7") (pin "7") (pinfunction "7_7") (pintype "passive"))
    )
    (net (code "210") (name "unconnected-(U$7-Pad8)") (class "Default")
      (node (ref "U$7") (pin "8") (pinfunction "8_8") (pintype "passive"))
    )
    (net (code "211") (name "unconnected-(U$7-Pad9)") (class "Default")
      (node (ref "U$7") (pin "9") (pinfunction "9_9") (pintype "passive"))
    )
    (net (code "212") (name "unconnected-(U$7-Pad10)") (class "Default")
      (node (ref "U$7") (pin "10") (pinfunction "10_10") (pintype "passive"))
    )
    (net (code "213") (name "unconnected-(U$7-Pad11)") (class "Default")
      (node (ref "U$7") (pin "11") (pinfunction "11_11") (pintype "passive"))
    )
    (net (code "214") (name "unconnected-(U$7-Pad12)") (class "Default")
      (node (ref "U$7") (pin "12") (pinfunction "12_12") (pintype "passive"))
    )
    (net (code "215") (name "unconnected-(U$7-Pad13)") (class "Default")
      (node (ref "U$7") (pin "13") (pinfunction "13_13") (pintype "passive"))
    )
    (net (code "216") (name "unconnected-(U$7-Pad14)") (class "Default")
      (node (ref "U$7") (pin "14") (pinfunction "14_14") (pintype "passive"))
    )
    (net (code "217") (name "unconnected-(U$7-Pad15)") (class "Default")
      (node (ref "U$7") (pin "15") (pinfunction "15_15") (pintype "passive"))
    )
    (net (code "218") (name "unconnected-(U$7-Pad16)") (class "Default")
      (node (ref "U$7") (pin "16") (pinfunction "16_16") (pintype "passive"))
    )
    (net (code "219") (name "unconnected-(U$7-Pad17)") (class "Default")
      (node (ref "U$7") (pin "17") (pinfunction "17_17") (pintype "passive"))
    )
    (net (code "220") (name "unconnected-(U$8-Pad1)") (class "Default")
      (node (ref "U$8") (pin "1") (pinfunction "1_1") (pintype "passive"))
    )
    (net (code "221") (name "unconnected-(U$8-Pad2)") (class "Default")
      (node (ref "U$8") (pin "2") (pinfunction "2_2") (pintype "passive"))
    )
    (net (code "222") (name "unconnected-(U$8-Pad3)") (class "Default")
      (node (ref "U$8") (pin "3") (pinfunction "3_3") (pintype "passive"))
    )
    (net (code "223") (name "unconnected-(U$8-Pad4)") (class "Default")
      (node (ref "U$8") (pin "4") (pinfunction "4_4") (pintype "passive"))
    )
    (net (code "224") (name "unconnected-(U$8-Pad5)") (class "Default")
      (node (ref "U$8") (pin "5") (pinfunction "5_5") (pintype "passive"))
    )
    (net (code "225") (name "unconnected-(U$8-Pad6)") (class "Default")
      (node (ref "U$8") (pin "6") (pinfunction "6_6") (pintype "passive"))
    )
    (net (code "226") (name "unconnected-(U$8-Pad7)") (class "Default")
      (node (ref "U$8") (pin "7") (pinfunction "7_7") (pintype "passive"))
    )
    (net (code "227") (name "unconnected-(U$8-Pad8)") (class "Default")
      (node (ref "U$8") (pin "8") (pinfunction "8_8") (pintype "passive"))
    )
    (net (code "228") (name "unconnected-(U$8-Pad9)") (class "Default")
      (node (ref "U$8") (pin "9") (pinfunction "9_9") (pintype "passive"))
    )
    (net (code "229") (name "unconnected-(U$8-Pad10)") (class "Default")
      (node (ref "U$8") (pin "10") (pinfunction "10_10") (pintype "passive"))
    )
    (net (code "230") (name "unconnected-(U$8-Pad11)") (class "Default")
      (node (ref "U$8") (pin "11") (pinfunction "11_11") (pintype "passive"))
    )
    (net (code "231") (name "unconnected-(U$8-Pad12)") (class "Default")
      (node (ref "U$8") (pin "12") (pinfunction "12_12") (pintype "passive"))
    )
    (net (code "232") (name "unconnected-(U$8-Pad13)") (class "Default")
      (node (ref "U$8") (pin "13") (pinfunction "13_13") (pintype "passive"))
    )
    (net (code "233") (name "unconnected-(U$8-Pad14)") (class "Default")
      (node (ref "U$8") (pin "14") (pinfunction "14_14") (pintype "passive"))
    )
    (net (code "234") (name "unconnected-(U$8-Pad15)") (class "Default")
      (node (ref "U$8") (pin "15") (pinfunction "15_15") (pintype "passive"))
    )
    (net (code "235") (name "unconnected-(U$8-Pad16)") (class "Default")
      (node (ref "U$8") (pin "16") (pinfunction "16_16") (pintype "passive"))
    )
    (net (code "236") (name "unconnected-(U$8-Pad17)") (class "Default")
      (node (ref "U$8") (pin "17") (pinfunction "17_17") (pintype "passive"))
    )
    (net (code "237") (name "unconnected-(U$9-Pad1)") (class "Default")
      (node (ref "U$9") (pin "1") (pinfunction "1_1") (pintype "passive"))
    )
    (net (code "238") (name "unconnected-(U$9-Pad2)") (class "Default")
      (node (ref "U$9") (pin "2") (pinfunction "2_2") (pintype "passive"))
    )
    (net (code "239") (name "unconnected-(U$9-Pad3)") (class "Default")
      (node (ref "U$9") (pin "3") (pinfunction "3_3") (pintype "passive"))
    )
    (net (code "240") (name "unconnected-(U$9-Pad4)") (class "Default")
      (node (ref "U$9") (pin "4") (pinfunction "4_4") (pintype "passive"))
    )
    (net (code "241") (name "unconnected-(U$9-Pad5)") (class "Default")
      (node (ref "U$9") (pin "5") (pinfunction "5_5") (pintype "passive"))
    )
    (net (code "242") (name "unconnected-(U$9-Pad6)") (class "Default")
      (node (ref "U$9") (pin "6") (pinfunction "6_6") (pintype "passive"))
    )
    (net (code "243") (name "unconnected-(U$9-Pad7)") (class "Default")
      (node (ref "U$9") (pin "7") (pinfunction "7_7") (pintype "passive"))
    )
    (net (code "244") (name "unconnected-(U$9-Pad8)") (class "Default")
      (node (ref "U$9") (pin "8") (pinfunction "8_8") (pintype "passive"))
    )
    (net (code "245") (name "unconnected-(U$9-Pad9)") (class "Default")
      (node (ref "U$9") (pin "9") (pinfunction "9_9") (pintype "passive"))
    )
    (net (code "246") (name "unconnected-(U$9-Pad10)") (class "Default")
      (node (ref "U$9") (pin "10") (pinfunction "10_10") (pintype "passive"))
    )
    (net (code "247") (name "unconnected-(U$9-Pad11)") (class "Default")
      (node (ref "U$9") (pin "11") (pinfunction "11_11") (pintype "passive"))
    )
    (net (code "248") (name "unconnected-(U$9-Pad12)") (class "Default")
      (node (ref "U$9") (pin "12") (pinfunction "12_12") (pintype "passive"))
    )
    (net (code "249") (name "unconnected-(U$9-Pad13)") (class "Default")
      (node (ref "U$9") (pin "13") (pinfunction "13_13") (pintype "passive"))
    )
    (net (code "250") (name "unconnected-(U$9-Pad14)") (class "Default")
      (node (ref "U$9") (pin "14") (pinfunction "14_14") (pintype "passive"))
    )
    (net (code "251") (name "unconnected-(U$9-Pad15)") (class "Default")
      (node (ref "U$9") (pin "15") (pinfunction "15_15") (pintype "passive"))
    )
    (net (code "252") (name "unconnected-(U$9-Pad16)") (class "Default")
      (node (ref "U$9") (pin "16") (pinfunction "16_16") (pintype "passive"))
    )
    (net (code "253") (name "unconnected-(U$9-Pad17)") (class "Default")
      (node (ref "U$9") (pin "17") (pinfunction "17_17") (pintype "passive"))
    )
    (net (code "254") (name "unconnected-(U$10-Pad1)") (class "Default")
      (node (ref "U$10") (pin "1") (pinfunction "1_1") (pintype "passive"))
    )
    (net (code "255") (name "unconnected-(U$10-Pad2)") (class "Default")
      (node (ref "U$10") (pin "2") (pinfunction "2_2") (pintype "passive"))
    )
    (net (code "256") (name "unconnected-(U$10-Pad3)") (class "Default")
      (node (ref "U$10") (pin "3") (pinfunction "3_3") (pintype "passive"))
    )
    (net (code "257") (name "unconnected-(U$10-Pad4)") (class "Default")
      (node (ref "U$10") (pin "4") (pinfunction "4_4") (pintype "passive"))
    )
    (net (code "258") (name "unconnected-(U$10-Pad5)") (class "Default")
      (node (ref "U$10") (pin "5") (pinfunction "5_5") (pintype "passive"))
    )
    (net (code "259") (name "unconnected-(U$10-Pad6)") (class "Default")
      (node (ref "U$10") (pin "6") (pinfunction "6_6") (pintype "passive"))
    )
    (net (code "260") (name "unconnected-(U$10-Pad7)") (class "Default")
      (node (ref "U$10") (pin "7") (pinfunction "7_7") (pintype "passive"))
    )
    (net (code "261") (name "unconnected-(U$10-Pad8)") (class "Default")
      (node (ref "U$10") (pin "8") (pinfunction "8_8") (pintype "passive"))
    )
    (net (code "262") (name "unconnected-(U$10-Pad9)") (class "Default")
      (node (ref "U$10") (pin "9") (pinfunction "9_9") (pintype "passive"))
    )
    (net (code "263") (name "unconnected-(U$10-Pad10)") (class "Default")
      (node (ref "U$10") (pin "10") (pinfunction "10_10") (pintype "passive"))
    )
    (net (code "264") (name "unconnected-(U$10-Pad11)") (class "Default")
      (node (ref "U$10") (pin "11") (pinfunction "11_11") (pintype "passive"))
    )
    (net (code "265") (name "unconnected-(U$10-Pad12)") (class "Default")
      (node (ref "U$10") (pin "12") (pinfunction "12_12") (pintype "passive"))
    )
    (net (code "266") (name "unconnected-(U$10-Pad13)") (class "Default")
      (node (ref "U$10") (pin "13") (pinfunction "13_13") (pintype "passive"))
    )
    (net (code "267") (name "unconnected-(U$10-Pad14)") (class "Default")
      (node (ref "U$10") (pin "14") (pinfunction "14_14") (pintype "passive"))
    )
    (net (code "268") (name "unconnected-(U$10-Pad15)") (class "Default")
      (node (ref "U$10") (pin "15") (pinfunction "15_15") (pintype "passive"))
    )
    (net (code "269") (name "unconnected-(U$10-Pad16)") (class "Default")
      (node (ref "U$10") (pin "16") (pinfunction "16_16") (pintype "passive"))
    )
    (net (code "270") (name "unconnected-(U$10-Pad17)") (class "Default")
      (node (ref "U$10") (pin "17") (pinfunction "17_17") (pintype "passive"))
    )
    (net (code "271") (name "unconnected-(U$11-Pad1)") (class "Default")
      (node (ref "U$11") (pin "1") (pinfunction "1_1") (pintype "passive"))
    )
    (net (code "272") (name "unconnected-(U$11-Pad2)") (class "Default")
      (node (ref "U$11") (pin "2") (pinfunction "2_2") (pintype "passive"))
    )
    (net (code "273") (name "unconnected-(U$11-Pad3)") (class "Default")
      (node (ref "U$11") (pin "3") (pinfunction "3_3") (pintype "passive"))
    )
    (net (code "274") (name "unconnected-(U$11-Pad4)") (class "Default")
      (node (ref "U$11") (pin "4") (pinfunction "4_4") (pintype "passive"))
    )
    (net (code "275") (name "unconnected-(U$11-Pad5)") (class "Default")
      (node (ref "U$11") (pin "5") (pinfunction "5_5") (pintype "passive"))
    )
    (net (code "276") (name "unconnected-(U$11-Pad6)") (class "Default")
      (node (ref "U$11") (pin "6") (pinfunction "6_6") (pintype "passive"))
    )
    (net (code "277") (name "unconnected-(U$11-Pad7)") (class "Default")
      (node (ref "U$11") (pin "7") (pinfunction "7_7") (pintype "passive"))
    )
    (net (code "278") (name "unconnected-(U$11-Pad8)") (class "Default")
      (node (ref "U$11") (pin "8") (pinfunction "8_8") (pintype "passive"))
    )
    (net (code "279") (name "unconnected-(U$11-Pad9)") (class "Default")
      (node (ref "U$11") (pin "9") (pinfunction "9_9") (pintype "passive"))
    )
    (net (code "280") (name "unconnected-(U$11-Pad10)") (class "Default")
      (node (ref "U$11") (pin "10") (pinfunction "10_10") (pintype "passive"))
    )
    (net (code "281") (name "unconnected-(U$11-Pad11)") (class "Default")
      (node (ref "U$11") (pin "11") (pinfunction "11_11") (pintype "passive"))
    )
    (net (code "282") (name "unconnected-(U$11-Pad12)") (class "Default")
      (node (ref "U$11") (pin "12") (pinfunction "12_12") (pintype "passive"))
    )
    (net (code "283") (name "unconnected-(U$11-Pad13)") (class "Default")
      (node (ref "U$11") (pin "13") (pinfunction "13_13") (pintype "passive"))
    )
    (net (code "284") (name "unconnected-(U$11-Pad14)") (class "Default")
      (node (ref "U$11") (pin "14") (pinfunction "14_14") (pintype "passive"))
    )
    (net (code "285") (name "unconnected-(U$11-Pad15)") (class "Default")
      (node (ref "U$11") (pin "15") (pinfunction "15_15") (pintype "passive"))
    )
    (net (code "286") (name "unconnected-(U$11-Pad16)") (class "Default")
      (node (ref "U$11") (pin "16") (pinfunction "16_16") (pintype "passive"))
    )
    (net (code "287") (name "unconnected-(U$11-Pad17)") (class "Default")
      (node (ref "U$11") (pin "17") (pinfunction "17_17") (pintype "passive"))
    )
    (net (code "288") (name "unconnected-(U$12-Pad1)") (class "Default")
      (node (ref "U$12") (pin "1") (pinfunction "1_1") (pintype "passive"))
    )
    (net (code "289") (name "unconnected-(U$12-Pad2)") (class "Default")
      (node (ref "U$12") (pin "2") (pinfunction "2_2") (pintype "passive"))
    )
    (net (code "290") (name "unconnected-(U$12-Pad3)") (class "Default")
      (node (ref "U$12") (pin "3") (pinfunction "3_3") (pintype "passive"))
    )
    (net (code "291") (name "unconnected-(U$12-Pad4)") (class "Default")
      (node (ref "U$12") (pin "4") (pinfunction "4_4") (pintype "passive"))
    )
    (net (code "292") (name "unconnected-(U$12-Pad5)") (class "Default")
      (node (ref "U$12") (pin "5") (pinfunction "5_5") (pintype "passive"))
    )
    (net (code "293") (name "unconnected-(U$12-Pad6)") (class "Default")
      (node (ref "U$12") (pin "6") (pinfunction "6_6") (pintype "passive"))
    )
    (net (code "294") (name "unconnected-(U$12-Pad7)") (class "Default")
      (node (ref "U$12") (pin "7") (pinfunction "7_7") (pintype "passive"))
    )
    (net (code "295") (name "unconnected-(U$12-Pad8)") (class "Default")
      (node (ref "U$12") (pin "8") (pinfunction "8_8") (pintype "passive"))
    )
    (net (code "296") (name "unconnected-(U$12-Pad9)") (class "Default")
      (node (ref "U$12") (pin "9") (pinfunction "9_9") (pintype "passive"))
    )
    (net (code "297") (name "unconnected-(U$12-Pad10)") (class "Default")
      (node (ref "U$12") (pin "10") (pinfunction "10_10") (pintype "passive"))
    )
    (net (code "298") (name "unconnected-(U$12-Pad11)") (class "Default")
      (node (ref "U$12") (pin "11") (pinfunction "11_11") (pintype "passive"))
    )
    (net (code "299") (name "unconnected-(U$12-Pad12)") (class "Default")
      (node (ref "U$12") (pin "12") (pinfunction "12_12") (pintype "passive"))
    )
    (net (code "300") (name "unconnected-(U$12-Pad13)") (class "Default")
      (node (ref "U$12") (pin "13") (pinfunction "13_13") (pintype "passive"))
    )
    (net (code "301") (name "unconnected-(U$12-Pad14)") (class "Default")
      (node (ref "U$12") (pin "14") (pinfunction "14_14") (pintype "passive"))
    )
    (net (code "302") (name "unconnected-(U$12-Pad15)") (class "Default")
      (node (ref "U$12") (pin "15") (pinfunction "15_15") (pintype "passive"))
    )
    (net (code "303") (name "unconnected-(U$12-Pad16)") (class "Default")
      (node (ref "U$12") (pin "16") (pinfunction "16_16") (pintype "passive"))
    )
    (net (code "304") (name "unconnected-(U$12-Pad17)") (class "Default")
      (node (ref "U$12") (pin "17") (pinfunction "17_17") (pintype "passive"))
    )
    (net (code "305") (name "unconnected-(U$13-Pad1)") (class "Default")
      (node (ref "U$13") (pin "1") (pinfunction "1_1") (pintype "passive"))
    )
    (net (code "306") (name "unconnected-(U$13-Pad2)") (class "Default")
      (node (ref "U$13") (pin "2") (pinfunction "2_2") (pintype "passive"))
    )
    (net (code "307") (name "unconnected-(U$13-Pad3)") (class "Default")
      (node (ref "U$13") (pin "3") (pinfunction "3_3") (pintype "passive"))
    )
    (net (code "308") (name "unconnected-(U$13-Pad4)") (class "Default")
      (node (ref "U$13") (pin "4") (pinfunction "4_4") (pintype "passive"))
    )
    (net (code "309") (name "unconnected-(U$13-Pad5)") (class "Default")
      (node (ref "U$13") (pin "5") (pinfunction "5_5") (pintype "passive"))
    )
    (net (code "310") (name "unconnected-(U$13-Pad6)") (class "Default")
      (node (ref "U$13") (pin "6") (pinfunction "6_6") (pintype "passive"))
    )
    (net (code "311") (name "unconnected-(U$13-Pad7)") (class "Default")
      (node (ref "U$13") (pin "7") (pinfunction "7_7") (pintype "passive"))
    )
    (net (code "312") (name "unconnected-(U$13-Pad8)") (class "Default")
      (node (ref "U$13") (pin "8") (pinfunction "8_8") (pintype "passive"))
    )
    (net (code "313") (name "unconnected-(U$13-Pad9)") (class "Default")
      (node (ref "U$13") (pin "9") (pinfunction "9_9") (pintype "passive"))
    )
    (net (code "314") (name "unconnected-(U$13-Pad10)") (class "Default")
      (node (ref "U$13") (pin "10") (pinfunction "10_10") (pintype "passive"))
    )
    (net (code "315") (name "unconnected-(U$13-Pad11)") (class "Default")
      (node (ref "U$13") (pin "11") (pinfunction "11_11") (pintype "passive"))
    )
    (net (code "316") (name "unconnected-(U$13-Pad12)") (class "Default")
      (node (ref "U$13") (pin "12") (pinfunction "12_12") (pintype "passive"))
    )
    (net (code "317") (name "unconnected-(U$13-Pad13)") (class "Default")
      (node (ref "U$13") (pin "13") (pinfunction "13_13") (pintype "passive"))
    )
    (net (code "318") (name "unconnected-(U$13-Pad14)") (class "Default")
      (node (ref "U$13") (pin "14") (pinfunction "14_14") (pintype "passive"))
    )
    (net (code "319") (name "unconnected-(U$13-Pad15)") (class "Default")
      (node (ref "U$13") (pin "15") (pinfunction "15_15") (pintype "passive"))
    )
    (net (code "320") (name "unconnected-(U$13-Pad16)") (class "Default")
      (node (ref "U$13") (pin "16") (pinfunction "16_16") (pintype "passive"))
    )
    (net (code "321") (name "unconnected-(U$13-Pad17)") (class "Default")
      (node (ref "U$13") (pin "17") (pinfunction "17_17") (pintype "passive"))
    )
    (net (code "322") (name "unconnected-(U$14-Pad1)") (class "Default")
      (node (ref "U$14") (pin "1") (pinfunction "1_1") (pintype "passive"))
    )
    (net (code "323") (name "unconnected-(U$14-Pad2)") (class "Default")
      (node (ref "U$14") (pin "2") (pinfunction "2_2") (pintype "passive"))
    )
    (net (code "324") (name "unconnected-(U$14-Pad3)") (class "Default")
      (node (ref "U$14") (pin "3") (pinfunction "3_3") (pintype "passive"))
    )
    (net (code "325") (name "unconnected-(U$14-Pad4)") (class "Default")
      (node (ref "U$14") (pin "4") (pinfunction "4_4") (pintype "passive"))
    )
    (net (code "326") (name "unconnected-(U$14-Pad5)") (class "Default")
      (node (ref "U$14") (pin "5") (pinfunction "5_5") (pintype "passive"))
    )
    (net (code "327") (name "unconnected-(U$14-Pad6)") (class "Default")
      (node (ref "U$14") (pin "6") (pinfunction "6_6") (pintype "passive"))
    )
    (net (code "328") (name "unconnected-(U$14-Pad7)") (class "Default")
      (node (ref "U$14") (pin "7") (pinfunction "7_7") (pintype "passive"))
    )
    (net (code "329") (name "unconnected-(U$14-Pad8)") (class "Default")
      (node (ref "U$14") (pin "8") (pinfunction "8_8") (pintype "passive"))
    )
    (net (code "330") (name "unconnected-(U$14-Pad9)") (class "Default")
      (node (ref "U$14") (pin "9") (pinfunction "9_9") (pintype "passive"))
    )
    (net (code "331") (name "unconnected-(U$14-Pad10)") (class "Default")
      (node (ref "U$14") (pin "10") (pinfunction "10_10") (pintype "passive"))
    )
    (net (code "332") (name "unconnected-(U$14-Pad11)") (class "Default")
      (node (ref "U$14") (pin "11") (pinfunction "11_11") (pintype "passive"))
    )
    (net (code "333") (name "unconnected-(U$14-Pad12)") (class "Default")
      (node (ref "U$14") (pin "12") (pinfunction "12_12") (pintype "passive"))
    )
    (net (code "334") (name "unconnected-(U$14-Pad13)") (class "Default")
      (node (ref "U$14") (pin "13") (pinfunction "13_13") (pintype "passive"))
    )
    (net (code "335") (name "unconnected-(U$14-Pad14)") (class "Default")
      (node (ref "U$14") (pin "14") (pinfunction "14_14") (pintype "passive"))
    )
    (net (code "336") (name "unconnected-(U$14-Pad15)") (class "Default")
      (node (ref "U$14") (pin "15") (pinfunction "15_15") (pintype "passive"))
    )
    (net (code "337") (name "unconnected-(U$14-Pad16)") (class "Default")
      (node (ref "U$14") (pin "16") (pinfunction "16_16") (pintype "passive"))
    )
    (net (code "338") (name "unconnected-(U$14-Pad17)") (class "Default")
      (node (ref "U$14") (pin "17") (pinfunction "17_17") (pintype "passive"))
    )
    (net (code "339") (name "unconnected-(U$15-Pad1)") (class "Default")
      (node (ref "U$15") (pin "1") (pinfunction "1_1") (pintype "passive"))
    )
    (net (code "340") (name "unconnected-(U$15-Pad2)") (class "Default")
      (node (ref "U$15") (pin "2") (pinfunction "2_2") (pintype "passive"))
    )
    (net (code "341") (name "unconnected-(U$15-Pad3)") (class "Default")
      (node (ref "U$15") (pin "3") (pinfunction "3_3") (pintype "passive"))
    )
    (net (code "342") (name "unconnected-(U$15-Pad4)") (class "Default")
      (node (ref "U$15") (pin "4") (pinfunction "4_4") (pintype "passive"))
    )
    (net (code "343") (name "unconnected-(U$15-Pad5)") (class "Default")
      (node (ref "U$15") (pin "5") (pinfunction "5_5") (pintype "passive"))
    )
    (net (code "344") (name "unconnected-(U$15-Pad6)") (class "Default")
      (node (ref "U$15") (pin "6") (pinfunction "6_6") (pintype "passive"))
    )
    (net (code "345") (name "unconnected-(U$15-Pad7)") (class "Default")
      (node (ref "U$15") (pin "7") (pinfunction "7_7") (pintype "passive"))
    )
    (net (code "346") (name "unconnected-(U$15-Pad8)") (class "Default")
      (node (ref "U$15") (pin "8") (pinfunction "8_8") (pintype "passive"))
    )
    (net (code "347") (name "unconnected-(U$15-Pad9)") (class "Default")
      (node (ref "U$15") (pin "9") (pinfunction "9_9") (pintype "passive"))
    )
    (net (code "348") (name "unconnected-(U$15-Pad10)") (class "Default")
      (node (ref "U$15") (pin "10") (pinfunction "10_10") (pintype "passive"))
    )
    (net (code "349") (name "unconnected-(U$15-Pad11)") (class "Default")
      (node (ref "U$15") (pin "11") (pinfunction "11_11") (pintype "passive"))
    )
    (net (code "350") (name "unconnected-(U$15-Pad12)") (class "Default")
      (node (ref "U$15") (pin "12") (pinfunction "12_12") (pintype "passive"))
    )
    (net (code "351") (name "unconnected-(U$15-Pad13)") (class "Default")
      (node (ref "U$15") (pin "13") (pinfunction "13_13") (pintype "passive"))
    )
    (net (code "352") (name "unconnected-(U$15-Pad14)") (class "Default")
      (node (ref "U$15") (pin "14") (pinfunction "14_14") (pintype "passive"))
    )
    (net (code "353") (name "unconnected-(U$15-Pad15)") (class "Default")
      (node (ref "U$15") (pin "15") (pinfunction "15_15") (pintype "passive"))
    )
    (net (code "354") (name "unconnected-(U$15-Pad16)") (class "Default")
      (node (ref "U$15") (pin "16") (pinfunction "16_16") (pintype "passive"))
    )
    (net (code "355") (name "unconnected-(U$15-Pad17)") (class "Default")
      (node (ref "U$15") (pin "17") (pinfunction "17_17") (pintype "passive"))
    )
    (net (code "356") (name "unconnected-(U$16-Pad1)") (class "Default")
      (node (ref "U$16") (pin "1") (pinfunction "1_1") (pintype "passive"))
    )
    (net (code "357") (name "unconnected-(U$16-Pad2)") (class "Default")
      (node (ref "U$16") (pin "2") (pinfunction "2_2") (pintype "passive"))
    )
    (net (code "358") (name "unconnected-(U$16-Pad3)") (class "Default")
      (node (ref "U$16") (pin "3") (pinfunction "3_3") (pintype "passive"))
    )
    (net (code "359") (name "unconnected-(U$16-Pad4)") (class "Default")
      (node (ref "U$16") (pin "4") (pinfunction "4_4") (pintype "passive"))
    )
    (net (code "360") (name "unconnected-(U$16-Pad5)") (class "Default")
      (node (ref "U$16") (pin "5") (pinfunction "5_5") (pintype "passive"))
    )
    (net (code "361") (name "unconnected-(U$16-Pad6)") (class "Default")
      (node (ref "U$16") (pin "6") (pinfunction "6_6") (pintype "passive"))
    )
    (net (code "362") (name "unconnected-(U$16-Pad7)") (class "Default")
      (node (ref "U$16") (pin "7") (pinfunction "7_7") (pintype "passive"))
    )
    (net (code "363") (name "unconnected-(U$16-Pad8)") (class "Default")
      (node (ref "U$16") (pin "8") (pinfunction "8_8") (pintype "passive"))
    )
    (net (code "364") (name "unconnected-(U$16-Pad9)") (class "Default")
      (node (ref "U$16") (pin "9") (pinfunction "9_9") (pintype "passive"))
    )
    (net (code "365") (name "unconnected-(U$16-Pad10)") (class "Default")
      (node (ref "U$16") (pin "10") (pinfunction "10_10") (pintype "passive"))
    )
    (net (code "366") (name "unconnected-(U$16-Pad11)") (class "Default")
      (node (ref "U$16") (pin "11") (pinfunction "11_11") (pintype "passive"))
    )
    (net (code "367") (name "unconnected-(U$16-Pad12)") (class "Default")
      (node (ref "U$16") (pin "12") (pinfunction "12_12") (pintype "passive"))
    )
    (net (code "368") (name "unconnected-(U$16-Pad13)") (class "Default")
      (node (ref "U$16") (pin "13") (pinfunction "13_13") (pintype "passive"))
    )
    (net (code "369") (name "unconnected-(U$16-Pad14)") (class "Default")
      (node (ref "U$16") (pin "14") (pinfunction "14_14") (pintype "passive"))
    )
    (net (code "370") (name "unconnected-(U$16-Pad15)") (class "Default")
      (node (ref "U$16") (pin "15") (pinfunction "15_15") (pintype "passive"))
    )
    (net (code "371") (name "unconnected-(U$16-Pad16)") (class "Default")
      (node (ref "U$16") (pin "16") (pinfunction "16_16") (pintype "passive"))
    )
    (net (code "372") (name "unconnected-(U$16-Pad17)") (class "Default")
      (node (ref "U$16") (pin "17") (pinfunction "17_17") (pintype "passive"))
    )
    (net (code "373") (name "unconnected-(U$18-Pad1)") (class "Default")
      (node (ref "U$18") (pin "1") (pinfunction "1_1") (pintype "passive"))
    )
    (net (code "374") (name "unconnected-(U$18-Pad2)") (class "Default")
      (node (ref "U$18") (pin "2") (pinfunction "2_2") (pintype "passive"))
    )
    (net (code "375") (name "unconnected-(U$18-Pad3)") (class "Default")
      (node (ref "U$18") (pin "3") (pinfunction "3_3") (pintype "passive"))
    )
    (net (code "376") (name "unconnected-(U$18-Pad4)") (class "Default")
      (node (ref "U$18") (pin "4") (pinfunction "4_4") (pintype "passive"))
    )
    (net (code "377") (name "unconnected-(U$18-Pad5)") (class "Default")
      (node (ref "U$18") (pin "5") (pinfunction "5_5") (pintype "passive"))
    )
    (net (code "378") (name "unconnected-(U$18-Pad6)") (class "Default")
      (node (ref "U$18") (pin "6") (pinfunction "6_6") (pintype "passive"))
    )
    (net (code "379") (name "unconnected-(U$18-Pad7)") (class "Default")
      (node (ref "U$18") (pin "7") (pinfunction "7_7") (pintype "passive"))
    )
    (net (code "380") (name "unconnected-(U$18-Pad8)") (class "Default")
      (node (ref "U$18") (pin "8") (pinfunction "8_8") (pintype "passive"))
    )
    (net (code "381") (name "unconnected-(U$18-Pad9)") (class "Default")
      (node (ref "U$18") (pin "9") (pinfunction "9_9") (pintype "passive"))
    )
    (net (code "382") (name "unconnected-(U$18-Pad10)") (class "Default")
      (node (ref "U$18") (pin "10") (pinfunction "10_10") (pintype "passive"))
    )
    (net (code "383") (name "unconnected-(U$18-Pad11)") (class "Default")
      (node (ref "U$18") (pin "11") (pinfunction "11_11") (pintype "passive"))
    )
    (net (code "384") (name "unconnected-(U$18-Pad12)") (class "Default")
      (node (ref "U$18") (pin "12") (pinfunction "12_12") (pintype "passive"))
    )
    (net (code "385") (name "unconnected-(U$18-Pad13)") (class "Default")
      (node (ref "U$18") (pin "13") (pinfunction "13_13") (pintype "passive"))
    )
    (net (code "386") (name "unconnected-(U$18-Pad14)") (class "Default")
      (node (ref "U$18") (pin "14") (pinfunction "14_14") (pintype "passive"))
    )
    (net (code "387") (name "unconnected-(U$18-Pad15)") (class "Default")
      (node (ref "U$18") (pin "15") (pinfunction "15_15") (pintype "passive"))
    )
    (net (code "388") (name "unconnected-(U$18-Pad16)") (class "Default")
      (node (ref "U$18") (pin "16") (pinfunction "16_16") (pintype "passive"))
    )
    (net (code "389") (name "unconnected-(U$18-Pad17)") (class "Default")
      (node (ref "U$18") (pin "17") (pinfunction "17_17") (pintype "passive"))
    )
    (net (code "390") (name "unconnected-(U$19-Pad1)") (class "Default")
      (node (ref "U$19") (pin "1") (pinfunction "1_1") (pintype "passive"))
    )
    (net (code "391") (name "unconnected-(U$19-Pad2)") (class "Default")
      (node (ref "U$19") (pin "2") (pinfunction "2_2") (pintype "passive"))
    )
    (net (code "392") (name "unconnected-(U$19-Pad3)") (class "Default")
      (node (ref "U$19") (pin "3") (pinfunction "3_3") (pintype "passive"))
    )
    (net (code "393") (name "unconnected-(U$19-Pad4)") (class "Default")
      (node (ref "U$19") (pin "4") (pinfunction "4_4") (pintype "passive"))
    )
    (net (code "394") (name "unconnected-(U$19-Pad5)") (class "Default")
      (node (ref "U$19") (pin "5") (pinfunction "5_5") (pintype "passive"))
    )
    (net (code "395") (name "unconnected-(U$19-Pad6)") (class "Default")
      (node (ref "U$19") (pin "6") (pinfunction "6_6") (pintype "passive"))
    )
    (net (code "396") (name "unconnected-(U$19-Pad7)") (class "Default")
      (node (ref "U$19") (pin "7") (pinfunction "7_7") (pintype "passive"))
    )
    (net (code "397") (name "unconnected-(U$19-Pad8)") (class "Default")
      (node (ref "U$19") (pin "8") (pinfunction "8_8") (pintype "passive"))
    )
    (net (code "398") (name "unconnected-(U$19-Pad9)") (class "Default")
      (node (ref "U$19") (pin "9") (pinfunction "9_9") (pintype "passive"))
    )
    (net (code "399") (name "unconnected-(U$19-Pad10)") (class "Default")
      (node (ref "U$19") (pin "10") (pinfunction "10_10") (pintype "passive"))
    )
    (net (code "400") (name "unconnected-(U$19-Pad11)") (class "Default")
      (node (ref "U$19") (pin "11") (pinfunction "11_11") (pintype "passive"))
    )
    (net (code "401") (name "unconnected-(U$19-Pad12)") (class "Default")
      (node (ref "U$19") (pin "12") (pinfunction "12_12") (pintype "passive"))
    )
    (net (code "402") (name "unconnected-(U$19-Pad13)") (class "Default")
      (node (ref "U$19") (pin "13") (pinfunction "13_13") (pintype "passive"))
    )
    (net (code "403") (name "unconnected-(U$19-Pad14)") (class "Default")
      (node (ref "U$19") (pin "14") (pinfunction "14_14") (pintype "passive"))
    )
    (net (code "404") (name "unconnected-(U$19-Pad15)") (class "Default")
      (node (ref "U$19") (pin "15") (pinfunction "15_15") (pintype "passive"))
    )
    (net (code "405") (name "unconnected-(U$19-Pad16)") (class "Default")
      (node (ref "U$19") (pin "16") (pinfunction "16_16") (pintype "passive"))
    )
    (net (code "406") (name "unconnected-(U$19-Pad17)") (class "Default")
      (node (ref "U$19") (pin "17") (pinfunction "17_17") (pintype "passive"))
    )
    (net (code "407") (name "unconnected-(U$20-Pad1)") (class "Default")
      (node (ref "U$20") (pin "1") (pinfunction "1_1") (pintype "passive"))
    )
    (net (code "408") (name "unconnected-(U$20-Pad2)") (class "Default")
      (node (ref "U$20") (pin "2") (pinfunction "2_2") (pintype "passive"))
    )
    (net (code "409") (name "unconnected-(U$20-Pad3)") (class "Default")
      (node (ref "U$20") (pin "3") (pinfunction "3_3") (pintype "passive"))
    )
    (net (code "410") (name "unconnected-(U$20-Pad4)") (class "Default")
      (node (ref "U$20") (pin "4") (pinfunction "4_4") (pintype "passive"))
    )
    (net (code "411") (name "unconnected-(U$20-Pad5)") (class "Default")
      (node (ref "U$20") (pin "5") (pinfunction "5_5") (pintype "passive"))
    )
    (net (code "412") (name "unconnected-(U$20-Pad6)") (class "Default")
      (node (ref "U$20") (pin "6") (pinfunction "6_6") (pintype "passive"))
    )
    (net (code "413") (name "unconnected-(U$20-Pad7)") (class "Default")
      (node (ref "U$20") (pin "7") (pinfunction "7_7") (pintype "passive"))
    )
    (net (code "414") (name "unconnected-(U$20-Pad8)") (class "Default")
      (node (ref "U$20") (pin "8") (pinfunction "8_8") (pintype "passive"))
    )
    (net (code "415") (name "unconnected-(U$20-Pad9)") (class "Default")
      (node (ref "U$20") (pin "9") (pinfunction "9_9") (pintype "passive"))
    )
    (net (code "416") (name "unconnected-(U$20-Pad10)") (class "Default")
      (node (ref "U$20") (pin "10") (pinfunction "10_10") (pintype "passive"))
    )
    (net (code "417") (name "unconnected-(U$20-Pad11)") (class "Default")
      (node (ref "U$20") (pin "11") (pinfunction "11_11") (pintype "passive"))
    )
    (net (code "418") (name "unconnected-(U$20-Pad12)") (class "Default")
      (node (ref "U$20") (pin "12") (pinfunction "12_12") (pintype "passive"))
    )
    (net (code "419") (name "unconnected-(U$20-Pad13)") (class "Default")
      (node (ref "U$20") (pin "13") (pinfunction "13_13") (pintype "passive"))
    )
    (net (code "420") (name "unconnected-(U$20-Pad14)") (class "Default")
      (node (ref "U$20") (pin "14") (pinfunction "14_14") (pintype "passive"))
    )
    (net (code "421") (name "unconnected-(U$20-Pad15)") (class "Default")
      (node (ref "U$20") (pin "15") (pinfunction "15_15") (pintype "passive"))
    )
    (net (code "422") (name "unconnected-(U$20-Pad16)") (class "Default")
      (node (ref "U$20") (pin "16") (pinfunction "16_16") (pintype "passive"))
    )
    (net (code "423") (name "unconnected-(U$20-Pad17)") (class "Default")
      (node (ref "U$20") (pin "17") (pinfunction "17_17") (pintype "passive"))
    )
    (net (code "424") (name "unconnected-(U$21-Pad1)") (class "Default")
      (node (ref "U$21") (pin "1") (pinfunction "1_1") (pintype "passive"))
    )
    (net (code "425") (name "unconnected-(U$21-Pad2)") (class "Default")
      (node (ref "U$21") (pin "2") (pinfunction "2_2") (pintype "passive"))
    )
    (net (code "426") (name "unconnected-(U$21-Pad3)") (class "Default")
      (node (ref "U$21") (pin "3") (pinfunction "3_3") (pintype "passive"))
    )
    (net (code "427") (name "unconnected-(U$21-Pad4)") (class "Default")
      (node (ref "U$21") (pin "4") (pinfunction "4_4") (pintype "passive"))
    )
    (net (code "428") (name "unconnected-(U$21-Pad5)") (class "Default")
      (node (ref "U$21") (pin "5") (pinfunction "5_5") (pintype "passive"))
    )
    (net (code "429") (name "unconnected-(U$21-Pad6)") (class "Default")
      (node (ref "U$21") (pin "6") (pinfunction "6_6") (pintype "passive"))
    )
    (net (code "430") (name "unconnected-(U$21-Pad7)") (class "Default")
      (node (ref "U$21") (pin "7") (pinfunction "7_7") (pintype "passive"))
    )
    (net (code "431") (name "unconnected-(U$21-Pad8)") (class "Default")
      (node (ref "U$21") (pin "8") (pinfunction "8_8") (pintype "passive"))
    )
    (net (code "432") (name "unconnected-(U$21-Pad9)") (class "Default")
      (node (ref "U$21") (pin "9") (pinfunction "9_9") (pintype "passive"))
    )
    (net (code "433") (name "unconnected-(U$21-Pad10)") (class "Default")
      (node (ref "U$21") (pin "10") (pinfunction "10_10") (pintype "passive"))
    )
    (net (code "434") (name "unconnected-(U$21-Pad11)") (class "Default")
      (node (ref "U$21") (pin "11") (pinfunction "11_11") (pintype "passive"))
    )
    (net (code "435") (name "unconnected-(U$21-Pad12)") (class "Default")
      (node (ref "U$21") (pin "12") (pinfunction "12_12") (pintype "passive"))
    )
    (net (code "436") (name "unconnected-(U$21-Pad13)") (class "Default")
      (node (ref "U$21") (pin "13") (pinfunction "13_13") (pintype "passive"))
    )
    (net (code "437") (name "unconnected-(U$21-Pad14)") (class "Default")
      (node (ref "U$21") (pin "14") (pinfunction "14_14") (pintype "passive"))
    )
    (net (code "438") (name "unconnected-(U$21-Pad15)") (class "Default")
      (node (ref "U$21") (pin "15") (pinfunction "15_15") (pintype "passive"))
    )
    (net (code "439") (name "unconnected-(U$21-Pad16)") (class "Default")
      (node (ref "U$21") (pin "16") (pinfunction "16_16") (pintype "passive"))
    )
    (net (code "440") (name "unconnected-(U$21-Pad17)") (class "Default")
      (node (ref "U$21") (pin "17") (pinfunction "17_17") (pintype "passive"))
    )
  )
)
